# Baja_PDU_004.net
KiCad netlist of a schematic drawn in Altium Designer
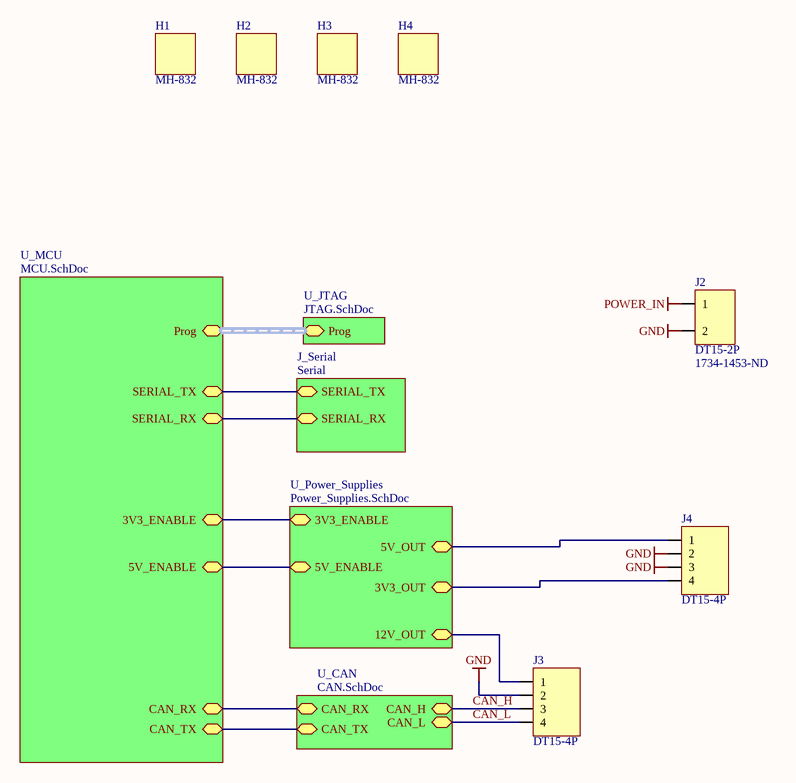
[diagram p0: Baja_PDU_004.SchDoc]

(export (version "E")
  (design (tool "Eeschema 10.0.6"))
  (components
    (comp (ref "H1")
      (value "MH-832")
      (footprint "MH-832")
      (libsource (lib "CornellBajaLibrary") (part "MH-832"))
    )
    (comp (ref "H2")
      (value "MH-832")
      (footprint "MH-832")
      (libsource (lib "CornellBajaLibrary") (part "MH-832"))
    )
    (comp (ref "H3")
      (value "MH-832")
      (footprint "MH-832")
      (libsource (lib "CornellBajaLibrary") (part "MH-832"))
    )
    (comp (ref "H4")
      (value "MH-832")
      (footprint "MH-832")
      (libsource (lib "CornellBajaLibrary") (part "MH-832"))
    )
    (comp (ref "J2")
      (value "DT15-2P")
      (footprint "Connector-DT15-2P")
      (fields (field (name "SUPPLIER PART NUMBER 1") "1734-1453-ND"))
      (libsource (lib "CornellBajaLibrary") (part "Connector-DT15-2P"))
    )
    (comp (ref "J3")
      (value "DT15-4P")
      (footprint "DT15-4P")
      (libsource (lib "CornellBajaLibrary") (part "Connector-DT15-4P"))
    )
    (comp (ref "J4")
      (value "DT15-4P")
      (footprint "DT15-4P")
      (libsource (lib "CornellBajaLibrary") (part "Connector-DT15-4P"))
    )
  )
  (nets
    (net (code "2") (name "/3V3_OUT") (class "Default")
      (node (ref "J4") (pin "4") (pinfunction "4_4") (pintype "passive"))
    )
    (net (code "4") (name "/5V_OUT") (class "Default")
      (node (ref "J4") (pin "1") (pinfunction "1_1") (pintype "passive"))
    )
    (net (code "5") (name "/12V_OUT") (class "Default")
      (node (ref "J3") (pin "1") (pinfunction "1_1") (pintype "passive"))
    )
    (net (code "6") (name "/CAN_H") (class "Default")
      (node (ref "J3") (pin "3") (pinfunction "3_3") (pintype "passive"))
    )
    (net (code "7") (name "/CAN_L") (class "Default")
      (node (ref "J3") (pin "4") (pinfunction "4_4") (pintype "passive"))
    )
    (net (code "13") (name "GND") (class "Default")
      (node (ref "J2") (pin "2") (pinfunction "2_2") (pintype "passive"))
      (node (ref "J3") (pin "2") (pinfunction "2_2") (pintype "passive"))
      (node (ref "J4") (pin "2") (pinfunction "2_2") (pintype "passive"))
      (node (ref "J4") (pin "3") (pinfunction "3_3") (pintype "passive"))
    )
    (net (code "14") (name "POWER_IN") (class "Default")
      (node (ref "J2") (pin "1") (pinfunction "1_1") (pintype "passive"))
    )
  )
)
